# plaque2.net
KiCad netlist of a schematic drawn in EAGLE
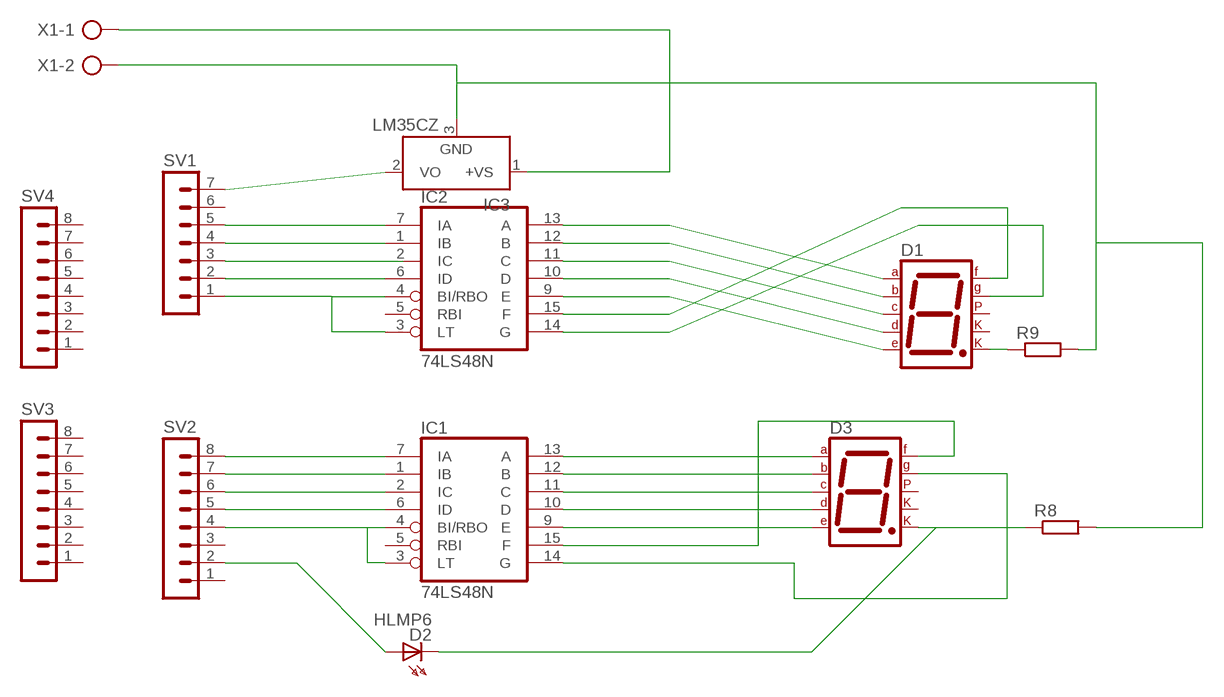
[diagram p0: schematic, sheet 1]

(export (version "E")
  (design (tool "Eeschema 10.0.6"))
  (components
    (comp (ref "D1")
      (value "7SEG-CK")
      (footprint "eagle-import:7SEG-13")
      (libsource (lib "eagle-import") (part "7SEG-CK"))
    )
    (comp (ref "D2")
      (value "HLMP6")
      (footprint "eagle-import:HLMP6")
      (fields (field (name "MF") "AGILENT TECHNOLOGIES") (field (name "MPN") "HLMP-6500"))
      (libsource (lib "eagle-import") (part "HLMP6"))
    )
    (comp (ref "D3")
      (value "7SEG-CK")
      (footprint "eagle-import:7SEG-13")
      (libsource (lib "eagle-import") (part "7SEG-CK"))
    )
    (comp (ref "IC1")
      (value "74LS48N")
      (footprint "eagle-import:DIL16")
      (libsource (lib "eagle-import") (part "7448NLS"))
    )
    (comp (ref "IC2")
      (value "74LS48N")
      (footprint "eagle-import:DIL16")
      (libsource (lib "eagle-import") (part "7448NLS"))
    )
    (comp (ref "IC3")
      (value "LM35CZ")
      (footprint "eagle-import:TO92")
      (libsource (lib "eagle-import") (part "LM35CZ"))
    )
    (comp (ref "R8")
      (value "R-EU_0204/7")
      (footprint "eagle-import:0204_7")
      (libsource (lib "eagle-import") (part "R-EU_0204/7"))
    )
    (comp (ref "R9")
      (value "R-EU_0204/7")
      (footprint "eagle-import:0204_7")
      (libsource (lib "eagle-import") (part "R-EU_0204/7"))
    )
    (comp (ref "SV1")
      (value "MA07-1")
      (footprint "eagle-import:MA07-1")
      (libsource (lib "eagle-import") (part "MA07-1"))
    )
    (comp (ref "SV2")
      (value "MA08-1")
      (footprint "eagle-import:MA08-1")
      (libsource (lib "eagle-import") (part "MA08-1"))
    )
    (comp (ref "SV3")
      (value "MA08-1")
      (footprint "eagle-import:MA08-1")
      (libsource (lib "eagle-import") (part "MA08-1"))
    )
    (comp (ref "SV4")
      (value "MA08-1")
      (footprint "eagle-import:MA08-1")
      (libsource (lib "eagle-import") (part "MA08-1"))
    )
    (comp (ref "X1")
      (value "AK500/2-H")
      (footprint "eagle-import:AK500_2-H")
      (libsource (lib "eagle-import") (part "AK500/2-H"))
    )
  )
  (nets
    (net (code "1") (name "Net-(D1-A)") (class "Default")
      (node (ref "D1") (pin "7") (pinfunction "A_7") (pintype "passive"))
      (node (ref "IC2") (pin "13") (pinfunction "A_13") (pintype "output"))
    )
    (net (code "2") (name "Net-(D1-B)") (class "Default")
      (node (ref "D1") (pin "6") (pinfunction "B_6") (pintype "passive"))
      (node (ref "IC2") (pin "12") (pinfunction "B_12") (pintype "output"))
    )
    (net (code "3") (name "Net-(D1-C)") (class "Default")
      (node (ref "D1") (pin "4") (pinfunction "C_4") (pintype "passive"))
      (node (ref "IC2") (pin "11") (pinfunction "C_11") (pintype "output"))
    )
    (net (code "4") (name "Net-(D1-CK2)") (class "Default")
      (node (ref "D1") (pin "8") (pinfunction "CK2_8") (pintype "passive"))
      (node (ref "R9") (pin "1") (pinfunction "1_1") (pintype "passive"))
    )
    (net (code "5") (name "Net-(D1-D)") (class "Default")
      (node (ref "D1") (pin "2") (pinfunction "D_2") (pintype "passive"))
      (node (ref "IC2") (pin "10") (pinfunction "D_10") (pintype "output"))
    )
    (net (code "6") (name "Net-(D1-E)") (class "Default")
      (node (ref "D1") (pin "1") (pinfunction "E_1") (pintype "passive"))
      (node (ref "IC2") (pin "9") (pinfunction "E_9") (pintype "output"))
    )
    (net (code "7") (name "Net-(D1-F)") (class "Default")
      (node (ref "D1") (pin "9") (pinfunction "F_9") (pintype "passive"))
      (node (ref "IC2") (pin "15") (pinfunction "F_15") (pintype "output"))
    )
    (net (code "8") (name "Net-(D1-G)") (class "Default")
      (node (ref "D1") (pin "10") (pinfunction "G_10") (pintype "passive"))
      (node (ref "IC2") (pin "14") (pinfunction "G_14") (pintype "output"))
    )
    (net (code "9") (name "Net-(D2-PadA)") (class "Default")
      (node (ref "D2") (pin "A") (pinfunction "A_A") (pintype "passive"))
      (node (ref "SV2") (pin "2") (pinfunction "2_2") (pintype "passive"))
    )
    (net (code "10") (name "Net-(D3-A)") (class "Default")
      (node (ref "D3") (pin "7") (pinfunction "A_7") (pintype "passive"))
      (node (ref "IC1") (pin "13") (pinfunction "A_13") (pintype "output"))
    )
    (net (code "11") (name "Net-(D3-B)") (class "Default")
      (node (ref "D3") (pin "6") (pinfunction "B_6") (pintype "passive"))
      (node (ref "IC1") (pin "12") (pinfunction "B_12") (pintype "output"))
    )
    (net (code "12") (name "Net-(D3-C)") (class "Default")
      (node (ref "D3") (pin "4") (pinfunction "C_4") (pintype "passive"))
      (node (ref "IC1") (pin "11") (pinfunction "C_11") (pintype "output"))
    )
    (net (code "13") (name "Net-(D3-CK2)") (class "Default")
      (node (ref "D2") (pin "K") (pinfunction "K_K") (pintype "passive"))
      (node (ref "D3") (pin "8") (pinfunction "CK2_8") (pintype "passive"))
      (node (ref "R8") (pin "1") (pinfunction "1_1") (pintype "passive"))
    )
    (net (code "14") (name "Net-(D3-D)") (class "Default")
      (node (ref "D3") (pin "2") (pinfunction "D_2") (pintype "passive"))
      (node (ref "IC1") (pin "10") (pinfunction "D_10") (pintype "output"))
    )
    (net (code "15") (name "Net-(D3-E)") (class "Default")
      (node (ref "D3") (pin "1") (pinfunction "E_1") (pintype "passive"))
      (node (ref "IC1") (pin "9") (pinfunction "E_9") (pintype "output"))
    )
    (net (code "16") (name "Net-(D3-F)") (class "Default")
      (node (ref "D3") (pin "9") (pinfunction "F_9") (pintype "passive"))
      (node (ref "IC1") (pin "15") (pinfunction "F_15") (pintype "output"))
    )
    (net (code "17") (name "Net-(D3-G)") (class "Default")
      (node (ref "D3") (pin "10") (pinfunction "G_10") (pintype "passive"))
      (node (ref "IC1") (pin "14") (pinfunction "G_14") (pintype "output"))
    )
    (net (code "18") (name "Net-(IC1A-BI{slash}RBO)") (class "Default")
      (node (ref "IC1") (pin "3") (pinfunction "LT_3") (pintype "input"))
      (node (ref "IC1") (pin "4") (pinfunction "BI/RBO_4") (pintype "input"))
      (node (ref "SV2") (pin "4") (pinfunction "4_4") (pintype "passive"))
    )
    (net (code "19") (name "Net-(IC1A-IA)") (class "Default")
      (node (ref "IC1") (pin "7") (pinfunction "IA_7") (pintype "input"))
      (node (ref "SV2") (pin "8") (pinfunction "8_8") (pintype "passive"))
    )
    (net (code "20") (name "Net-(IC1A-IB)") (class "Default")
      (node (ref "IC1") (pin "1") (pinfunction "IB_1") (pintype "input"))
      (node (ref "SV2") (pin "7") (pinfunction "7_7") (pintype "passive"))
    )
    (net (code "21") (name "Net-(IC1A-IC)") (class "Default")
      (node (ref "IC1") (pin "2") (pinfunction "IC_2") (pintype "input"))
      (node (ref "SV2") (pin "6") (pinfunction "6_6") (pintype "passive"))
    )
    (net (code "22") (name "Net-(IC1A-ID)") (class "Default")
      (node (ref "IC1") (pin "6") (pinfunction "ID_6") (pintype "input"))
      (node (ref "SV2") (pin "5") (pinfunction "5_5") (pintype "passive"))
    )
    (net (code "23") (name "Net-(IC2A-BI{slash}RBO)") (class "Default")
      (node (ref "IC2") (pin "3") (pinfunction "LT_3") (pintype "input"))
      (node (ref "IC2") (pin "4") (pinfunction "BI/RBO_4") (pintype "input"))
      (node (ref "SV1") (pin "1") (pinfunction "1_1") (pintype "passive"))
    )
    (net (code "24") (name "Net-(IC2A-IA)") (class "Default")
      (node (ref "IC2") (pin "7") (pinfunction "IA_7") (pintype "input"))
      (node (ref "SV1") (pin "5") (pinfunction "5_5") (pintype "passive"))
    )
    (net (code "25") (name "Net-(IC2A-IB)") (class "Default")
      (node (ref "IC2") (pin "1") (pinfunction "IB_1") (pintype "input"))
      (node (ref "SV1") (pin "4") (pinfunction "4_4") (pintype "passive"))
    )
    (net (code "26") (name "Net-(IC2A-ID)") (class "Default")
      (node (ref "IC2") (pin "6") (pinfunction "ID_6") (pintype "input"))
      (node (ref "SV1") (pin "2") (pinfunction "2_2") (pintype "passive"))
    )
    (net (code "27") (name "Net-(IC3-+VS)") (class "Default")
      (node (ref "IC3") (pin "1") (pinfunction "+VS_1") (pintype "input"))
      (node (ref "X1") (pin "1") (pinfunction "KL_1") (pintype "passive"))
    )
    (net (code "28") (name "Net-(IC3-GND)") (class "Default")
      (node (ref "IC3") (pin "3") (pinfunction "GND_3") (pintype "power_in"))
      (node (ref "R8") (pin "2") (pinfunction "2_2") (pintype "passive"))
      (node (ref "R9") (pin "2") (pinfunction "2_2") (pintype "passive"))
      (node (ref "X1") (pin "2") (pinfunction "KL_2") (pintype "passive"))
    )
    (net (code "29") (name "Net-(IC3-VO)") (class "Default")
      (node (ref "IC3") (pin "2") (pinfunction "VO_2") (pintype "input"))
      (node (ref "SV1") (pin "7") (pinfunction "7_7") (pintype "passive"))
    )
    (net (code "30") (name "unconnected-(D1-CK1-Pad3)") (class "Default")
      (node (ref "D1") (pin "3") (pinfunction "CK1_3") (pintype "passive"))
    )
    (net (code "31") (name "unconnected-(D1-DP-Pad5)") (class "Default")
      (node (ref "D1") (pin "5") (pinfunction "DP_5") (pintype "passive"))
    )
    (net (code "32") (name "unconnected-(D3-CK1-Pad3)") (class "Default")
      (node (ref "D3") (pin "3") (pinfunction "CK1_3") (pintype "passive"))
    )
    (net (code "33") (name "unconnected-(D3-DP-Pad5)") (class "Default")
      (node (ref "D3") (pin "5") (pinfunction "DP_5") (pintype "passive"))
    )
    (net (code "34") (name "unconnected-(IC1A-RBI-Pad5)") (class "Default")
      (node (ref "IC1") (pin "5") (pinfunction "RBI_5") (pintype "input"))
    )
    (net (code "35") (name "unconnected-(IC2A-IC-Pad2)") (class "Default")
      (node (ref "IC2") (pin "2") (pinfunction "IC_2") (pintype "input"))
    )
    (net (code "36") (name "unconnected-(IC2A-RBI-Pad5)") (class "Default")
      (node (ref "IC2") (pin "5") (pinfunction "RBI_5") (pintype "input"))
    )
    (net (code "37") (name "unconnected-(SV1-Pad3)") (class "Default")
      (node (ref "SV1") (pin "3") (pinfunction "3_3") (pintype "passive"))
    )
    (net (code "38") (name "unconnected-(SV1-Pad6)") (class "Default")
      (node (ref "SV1") (pin "6") (pinfunction "6_6") (pintype "passive"))
    )
    (net (code "39") (name "unconnected-(SV2-Pad1)") (class "Default")
      (node (ref "SV2") (pin "1") (pinfunction "1_1") (pintype "passive"))
    )
    (net (code "40") (name "unconnected-(SV2-Pad3)") (class "Default")
      (node (ref "SV2") (pin "3") (pinfunction "3_3") (pintype "passive"))
    )
    (net (code "41") (name "unconnected-(SV3-Pad1)") (class "Default")
      (node (ref "SV3") (pin "1") (pinfunction "1_1") (pintype "passive"))
    )
    (net (code "42") (name "unconnected-(SV3-Pad2)") (class "Default")
      (node (ref "SV3") (pin "2") (pinfunction "2_2") (pintype "passive"))
    )
    (net (code "43") (name "unconnected-(SV3-Pad3)") (class "Default")
      (node (ref "SV3") (pin "3") (pinfunction "3_3") (pintype "passive"))
    )
    (net (code "44") (name "unconnected-(SV3-Pad4)") (class "Default")
      (node (ref "SV3") (pin "4") (pinfunction "4_4") (pintype "passive"))
    )
    (net (code "45") (name "unconnected-(SV3-Pad5)") (class "Default")
      (node (ref "SV3") (pin "5") (pinfunction "5_5") (pintype "passive"))
    )
    (net (code "46") (name "unconnected-(SV3-Pad6)") (class "Default")
      (node (ref "SV3") (pin "6") (pinfunction "6_6") (pintype "passive"))
    )
    (net (code "47") (name "unconnected-(SV3-Pad7)") (class "Default")
      (node (ref "SV3") (pin "7") (pinfunction "7_7") (pintype "passive"))
    )
    (net (code "48") (name "unconnected-(SV3-Pad8)") (class "Default")
      (node (ref "SV3") (pin "8") (pinfunction "8_8") (pintype "passive"))
    )
    (net (code "49") (name "unconnected-(SV4-Pad1)") (class "Default")
      (node (ref "SV4") (pin "1") (pinfunction "1_1") (pintype "passive"))
    )
    (net (code "50") (name "unconnected-(SV4-Pad2)") (class "Default")
      (node (ref "SV4") (pin "2") (pinfunction "2_2") (pintype "passive"))
    )
    (net (code "51") (name "unconnected-(SV4-Pad3)") (class "Default")
      (node (ref "SV4") (pin "3") (pinfunction "3_3") (pintype "passive"))
    )
    (net (code "52") (name "unconnected-(SV4-Pad4)") (class "Default")
      (node (ref "SV4") (pin "4") (pinfunction "4_4") (pintype "passive"))
    )
    (net (code "53") (name "unconnected-(SV4-Pad5)") (class "Default")
      (node (ref "SV4") (pin "5") (pinfunction "5_5") (pintype "passive"))
    )
    (net (code "54") (name "unconnected-(SV4-Pad6)") (class "Default")
      (node (ref "SV4") (pin "6") (pinfunction "6_6") (pintype "passive"))
    )
    (net (code "55") (name "unconnected-(SV4-Pad7)") (class "Default")
      (node (ref "SV4") (pin "7") (pinfunction "7_7") (pintype "passive"))
    )
    (net (code "56") (name "unconnected-(SV4-Pad8)") (class "Default")
      (node (ref "SV4") (pin "8") (pinfunction "8_8") (pintype "passive"))
    )
  )
)
